# celula_de_carga.net
KiCad netlist of a schematic drawn in EAGLE
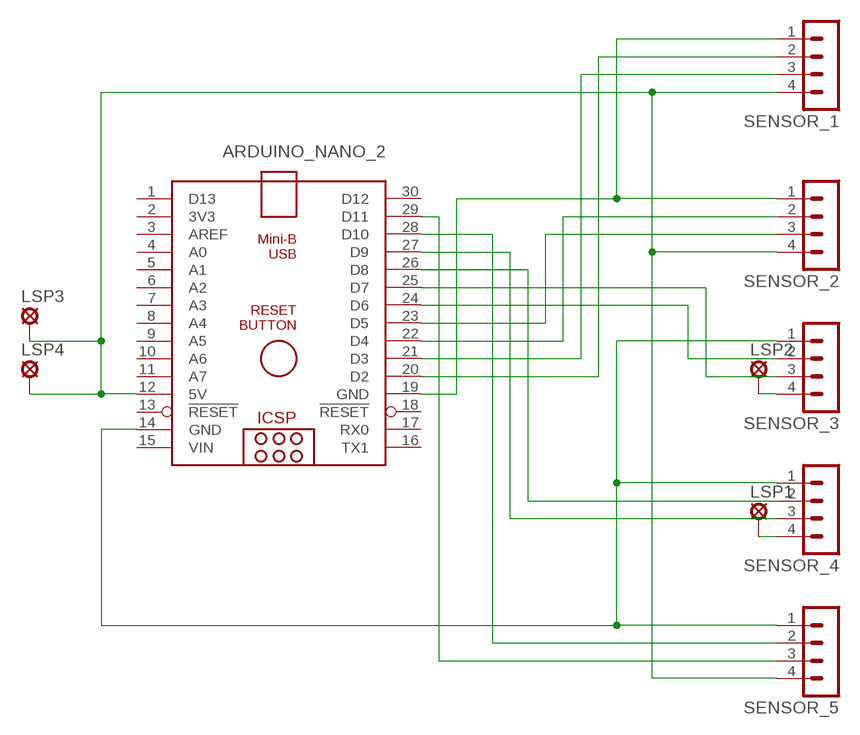
[diagram p0: schematic, sheet 1]

(export (version "E")
  (design (tool "Eeschema 10.0.6"))
  (components
    (comp (ref "ARDUINO_NANO_2")
      (value "ARDUINO_NANO")
      (footprint "eagle-import:ARDUINO_NANO")
      (libsource (lib "eagle-import") (part "ARDUINO_NANO"))
    )
    (comp (ref "LSP1")
      (value "LSP10")
      (footprint "eagle-import:LSP10")
      (libsource (lib "eagle-import") (part "LSP10"))
    )
    (comp (ref "LSP2")
      (value "LSP10")
      (footprint "eagle-import:LSP10")
      (libsource (lib "eagle-import") (part "LSP10"))
    )
    (comp (ref "LSP3")
      (value "LSP10")
      (footprint "eagle-import:LSP10")
      (libsource (lib "eagle-import") (part "LSP10"))
    )
    (comp (ref "LSP4")
      (value "LSP10")
      (footprint "eagle-import:LSP10")
      (libsource (lib "eagle-import") (part "LSP10"))
    )
    (comp (ref "SENSOR_1")
      (value "MA04-1")
      (footprint "eagle-import:MA04-1")
      (libsource (lib "eagle-import") (part "MA04-1"))
    )
    (comp (ref "SENSOR_2")
      (value "MA04-1")
      (footprint "eagle-import:MA04-1")
      (libsource (lib "eagle-import") (part "MA04-1"))
    )
    (comp (ref "SENSOR_3")
      (value "MA04-1")
      (footprint "eagle-import:MA04-1")
      (libsource (lib "eagle-import") (part "MA04-1"))
    )
    (comp (ref "SENSOR_4")
      (value "MA04-1")
      (footprint "eagle-import:MA04-1")
      (libsource (lib "eagle-import") (part "MA04-1"))
    )
    (comp (ref "SENSOR_5")
      (value "MA04-1")
      (footprint "eagle-import:MA04-1")
      (libsource (lib "eagle-import") (part "MA04-1"))
    )
  )
  (nets
    (net (code "1") (name "/VIN") (class "Default")
      (node (ref "ARDUINO_NANO_2") (pin "15") (pinfunction "VIN_15") (pintype "power_in"))
    )
    (net (code "2") (name "Net-(ARDUINO_NANO_2-5V)") (class "Default")
      (node (ref "ARDUINO_NANO_2") (pin "12") (pinfunction "5V_12") (pintype "power_in"))
      (node (ref "LSP3") (pin "MP") (pinfunction "MP_MP") (pintype "passive"))
      (node (ref "LSP4") (pin "MP") (pinfunction "MP_MP") (pintype "passive"))
      (node (ref "SENSOR_1") (pin "4") (pinfunction "4_4") (pintype "passive"))
      (node (ref "SENSOR_2") (pin "4") (pinfunction "4_4") (pintype "passive"))
      (node (ref "SENSOR_5") (pin "4") (pinfunction "4_4") (pintype "passive"))
    )
    (net (code "3") (name "Net-(ARDUINO_NANO_2-D2)") (class "Default")
      (node (ref "ARDUINO_NANO_2") (pin "20") (pinfunction "D2_20") (pintype "bidirectional"))
      (node (ref "SENSOR_1") (pin "2") (pinfunction "2_2") (pintype "passive"))
    )
    (net (code "4") (name "Net-(ARDUINO_NANO_2-D3)") (class "Default")
      (node (ref "ARDUINO_NANO_2") (pin "21") (pinfunction "D3_21") (pintype "bidirectional"))
      (node (ref "SENSOR_1") (pin "3") (pinfunction "3_3") (pintype "passive"))
    )
    (net (code "5") (name "Net-(ARDUINO_NANO_2-D4)") (class "Default")
      (node (ref "ARDUINO_NANO_2") (pin "22") (pinfunction "D4_22") (pintype "bidirectional"))
      (node (ref "SENSOR_2") (pin "2") (pinfunction "2_2") (pintype "passive"))
    )
    (net (code "6") (name "Net-(ARDUINO_NANO_2-D5)") (class "Default")
      (node (ref "ARDUINO_NANO_2") (pin "23") (pinfunction "D5_23") (pintype "bidirectional"))
      (node (ref "SENSOR_2") (pin "3") (pinfunction "3_3") (pintype "passive"))
    )
    (net (code "7") (name "Net-(ARDUINO_NANO_2-D6)") (class "Default")
      (node (ref "ARDUINO_NANO_2") (pin "24") (pinfunction "D6_24") (pintype "bidirectional"))
      (node (ref "SENSOR_3") (pin "2") (pinfunction "2_2") (pintype "passive"))
    )
    (net (code "8") (name "Net-(ARDUINO_NANO_2-D7)") (class "Default")
      (node (ref "ARDUINO_NANO_2") (pin "25") (pinfunction "D7_25") (pintype "bidirectional"))
      (node (ref "SENSOR_3") (pin "3") (pinfunction "3_3") (pintype "passive"))
    )
    (net (code "9") (name "Net-(ARDUINO_NANO_2-D8)") (class "Default")
      (node (ref "ARDUINO_NANO_2") (pin "26") (pinfunction "D8_26") (pintype "bidirectional"))
      (node (ref "SENSOR_4") (pin "2") (pinfunction "2_2") (pintype "passive"))
    )
    (net (code "10") (name "Net-(ARDUINO_NANO_2-D9)") (class "Default")
      (node (ref "ARDUINO_NANO_2") (pin "27") (pinfunction "D9_27") (pintype "bidirectional"))
      (node (ref "SENSOR_4") (pin "3") (pinfunction "3_3") (pintype "passive"))
    )
    (net (code "11") (name "Net-(ARDUINO_NANO_2-D10)") (class "Default")
      (node (ref "ARDUINO_NANO_2") (pin "28") (pinfunction "D10_28") (pintype "bidirectional"))
      (node (ref "SENSOR_5") (pin "2") (pinfunction "2_2") (pintype "passive"))
    )
    (net (code "12") (name "Net-(ARDUINO_NANO_2-D11)") (class "Default")
      (node (ref "ARDUINO_NANO_2") (pin "29") (pinfunction "D11_29") (pintype "bidirectional"))
      (node (ref "SENSOR_5") (pin "3") (pinfunction "3_3") (pintype "passive"))
    )
    (net (code "13") (name "Net-(ARDUINO_NANO_2-GND-Pad14)") (class "Default")
      (node (ref "ARDUINO_NANO_2") (pin "14") (pinfunction "GND_14") (pintype "power_in"))
      (node (ref "SENSOR_3") (pin "1") (pinfunction "1_1") (pintype "passive"))
      (node (ref "SENSOR_4") (pin "1") (pinfunction "1_1") (pintype "passive"))
      (node (ref "SENSOR_5") (pin "1") (pinfunction "1_1") (pintype "passive"))
    )
    (net (code "14") (name "Net-(ARDUINO_NANO_2-GND-Pad19)") (class "Default")
      (node (ref "ARDUINO_NANO_2") (pin "19") (pinfunction "GND_19") (pintype "power_in"))
      (node (ref "SENSOR_1") (pin "1") (pinfunction "1_1") (pintype "passive"))
      (node (ref "SENSOR_2") (pin "1") (pinfunction "1_1") (pintype "passive"))
    )
    (net (code "15") (name "Net-(LSP1-PadMP)") (class "Default")
      (node (ref "LSP1") (pin "MP") (pinfunction "MP_MP") (pintype "passive"))
      (node (ref "SENSOR_4") (pin "4") (pinfunction "4_4") (pintype "passive"))
    )
    (net (code "16") (name "Net-(LSP2-PadMP)") (class "Default")
      (node (ref "LSP2") (pin "MP") (pinfunction "MP_MP") (pintype "passive"))
      (node (ref "SENSOR_3") (pin "4") (pinfunction "4_4") (pintype "passive"))
    )
    (net (code "17") (name "unconnected-(ARDUINO_NANO_2-3V3-Pad2)") (class "Default")
      (node (ref "ARDUINO_NANO_2") (pin "2") (pinfunction "3V3_2") (pintype "output"))
    )
    (net (code "18") (name "unconnected-(ARDUINO_NANO_2-A0-Pad4)") (class "Default")
      (node (ref "ARDUINO_NANO_2") (pin "4") (pinfunction "A0_4") (pintype "bidirectional"))
    )
    (net (code "19") (name "unconnected-(ARDUINO_NANO_2-A1-Pad5)") (class "Default")
      (node (ref "ARDUINO_NANO_2") (pin "5") (pinfunction "A1_5") (pintype "bidirectional"))
    )
    (net (code "20") (name "unconnected-(ARDUINO_NANO_2-A2-Pad6)") (class "Default")
      (node (ref "ARDUINO_NANO_2") (pin "6") (pinfunction "A2_6") (pintype "bidirectional"))
    )
    (net (code "21") (name "unconnected-(ARDUINO_NANO_2-A3-Pad7)") (class "Default")
      (node (ref "ARDUINO_NANO_2") (pin "7") (pinfunction "A3_7") (pintype "bidirectional"))
    )
    (net (code "22") (name "unconnected-(ARDUINO_NANO_2-A4-Pad8)") (class "Default")
      (node (ref "ARDUINO_NANO_2") (pin "8") (pinfunction "A4_8") (pintype "bidirectional"))
    )
    (net (code "23") (name "unconnected-(ARDUINO_NANO_2-A5-Pad9)") (class "Default")
      (node (ref "ARDUINO_NANO_2") (pin "9") (pinfunction "A5_9") (pintype "bidirectional"))
    )
    (net (code "24") (name "unconnected-(ARDUINO_NANO_2-A6-Pad10)") (class "Default")
      (node (ref "ARDUINO_NANO_2") (pin "10") (pinfunction "A6_10") (pintype "bidirectional"))
    )
    (net (code "25") (name "unconnected-(ARDUINO_NANO_2-A7-Pad11)") (class "Default")
      (node (ref "ARDUINO_NANO_2") (pin "11") (pinfunction "A7_11") (pintype "bidirectional"))
    )
    (net (code "26") (name "unconnected-(ARDUINO_NANO_2-AREF-Pad3)") (class "Default")
      (node (ref "ARDUINO_NANO_2") (pin "3") (pinfunction "AREF_3") (pintype "input"))
    )
    (net (code "27") (name "unconnected-(ARDUINO_NANO_2-D12-Pad30)") (class "Default")
      (node (ref "ARDUINO_NANO_2") (pin "30") (pinfunction "D12_30") (pintype "bidirectional"))
    )
    (net (code "28") (name "unconnected-(ARDUINO_NANO_2-D13-Pad1)") (class "Default")
      (node (ref "ARDUINO_NANO_2") (pin "1") (pinfunction "D13_1") (pintype "bidirectional"))
    )
    (net (code "29") (name "unconnected-(ARDUINO_NANO_2-RX0-Pad17)") (class "Default")
      (node (ref "ARDUINO_NANO_2") (pin "17") (pinfunction "RX0_17") (pintype "bidirectional"))
    )
    (net (code "30") (name "unconnected-(ARDUINO_NANO_2-TX1-Pad16)") (class "Default")
      (node (ref "ARDUINO_NANO_2") (pin "16") (pinfunction "TX1_16") (pintype "bidirectional"))
    )
    (net (code "31") (name "unconnected-(ARDUINO_NANO_2-~{RESET}-Pad13)") (class "Default")
      (node (ref "ARDUINO_NANO_2") (pin "13") (pinfunction "~{RESET}_13") (pintype "input"))
    )
    (net (code "32") (name "unconnected-(ARDUINO_NANO_2-~{RESET}-Pad18)") (class "Default")
      (node (ref "ARDUINO_NANO_2") (pin "18") (pinfunction "~{RESET}_18") (pintype "input"))
    )
  )
)
